# pololuLaserDrv.net
KiCad netlist of a schematic drawn in EAGLE
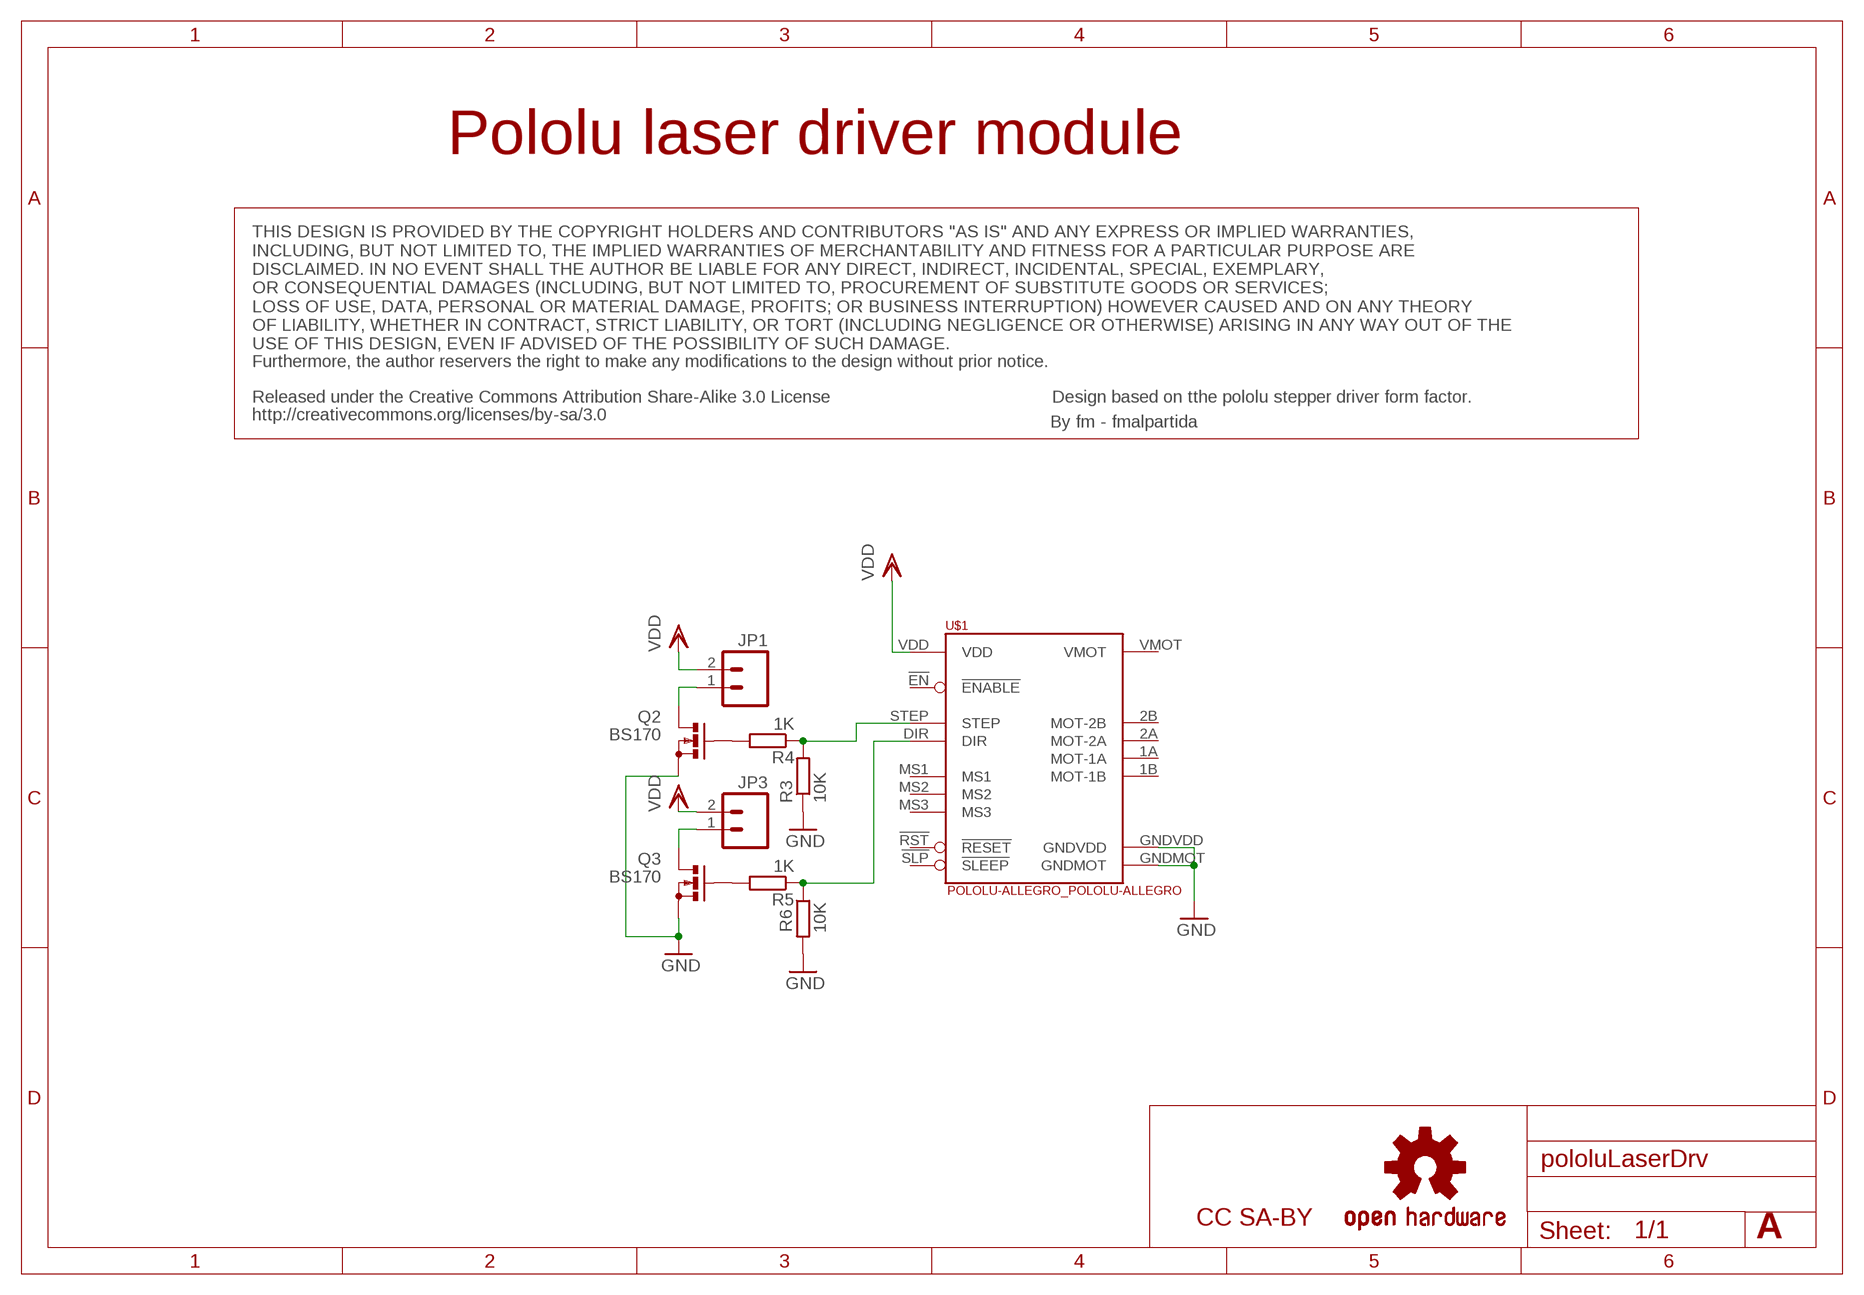
[diagram p0: schematic, sheet 1]

(export (version "E")
  (design (tool "Eeschema 10.0.6"))
  (components
    (comp (ref "JP1")
      (value "M02PTH")
      (footprint "eagle-import:1X02")
      (libsource (lib "eagle-import") (part "M02PTH"))
    )
    (comp (ref "JP3")
      (value "M02PTH")
      (footprint "eagle-import:1X02")
      (libsource (lib "eagle-import") (part "M02PTH"))
    )
    (comp (ref "Q2")
      (value "BS170")
      (footprint "eagle-import:SOT54E")
      (libsource (lib "eagle-import") (part "BS170"))
    )
    (comp (ref "Q3")
      (value "BS170")
      (footprint "eagle-import:SOT54E")
      (libsource (lib "eagle-import") (part "BS170"))
    )
    (comp (ref "R3")
      (value "10K")
      (footprint "eagle-import:0204_5")
      (libsource (lib "eagle-import") (part "R-EU_0204/5"))
    )
    (comp (ref "R4")
      (value "1K")
      (footprint "eagle-import:0204_5")
      (libsource (lib "eagle-import") (part "R-EU_0204/5"))
    )
    (comp (ref "R5")
      (value "1K")
      (footprint "eagle-import:0204_5")
      (libsource (lib "eagle-import") (part "R-EU_0204/5"))
    )
    (comp (ref "R6")
      (value "10K")
      (footprint "eagle-import:0204_5")
      (libsource (lib "eagle-import") (part "R-EU_0204/5"))
    )
    (comp (ref "U$1")
      (value "POLOLU-ALLEGRO_POLOLU-ALLEGRO")
      (footprint "eagle-import:POLOLU-ALLEGRO_POLOLU-ALLEGRO-PTH")
      (libsource (lib "eagle-import") (part "POLOLU-ALLEGRO_POLOLU-ALLEGRO"))
    )
    (comp (ref "U$2")
      (value "OSHW-LOGOS")
      (footprint "eagle-import:OSHW-LOGO-S")
      (libsource (lib "eagle-import") (part "OSHW-LOGOS"))
    )
  )
  (nets
    (net (code "1") (name "/MOT-1A") (class "Default")
      (node (ref "U$1") (pin "1A") (pinfunction "MOT-1A_1A") (pintype "power_in"))
    )
    (net (code "2") (name "/MOT-1B") (class "Default")
      (node (ref "U$1") (pin "1B") (pinfunction "MOT-1B_1B") (pintype "power_in"))
    )
    (net (code "3") (name "/MOT-2A") (class "Default")
      (node (ref "U$1") (pin "2A") (pinfunction "MOT-2A_2A") (pintype "power_in"))
    )
    (net (code "4") (name "/MOT-2B") (class "Default")
      (node (ref "U$1") (pin "2B") (pinfunction "MOT-2B_2B") (pintype "power_in"))
    )
    (net (code "5") (name "/VMOT") (class "Default")
      (node (ref "U$1") (pin "VMOT") (pinfunction "VMOT_VMOT") (pintype "power_in"))
    )
    (net (code "6") (name "GND") (class "Default")
      (node (ref "Q2") (pin "S") (pinfunction "S_S") (pintype "passive"))
      (node (ref "Q3") (pin "S") (pinfunction "S_S") (pintype "passive"))
      (node (ref "R3") (pin "1") (pinfunction "1_1") (pintype "passive"))
      (node (ref "R6") (pin "2") (pinfunction "2_2") (pintype "passive"))
      (node (ref "U$1") (pin "GNDMOT") (pinfunction "GNDMOT_GNDMOT") (pintype "power_in"))
      (node (ref "U$1") (pin "GNDVDD") (pinfunction "GNDVDD_GNDVDD") (pintype "power_in"))
    )
    (net (code "7") (name "Net-(JP1-Pad1)") (class "Default")
      (node (ref "JP1") (pin "1") (pinfunction "1_1") (pintype "passive"))
      (node (ref "Q2") (pin "D") (pinfunction "D_D") (pintype "passive"))
    )
    (net (code "8") (name "Net-(JP3-Pad1)") (class "Default")
      (node (ref "JP3") (pin "1") (pinfunction "1_1") (pintype "passive"))
      (node (ref "Q3") (pin "D") (pinfunction "D_D") (pintype "passive"))
    )
    (net (code "9") (name "Net-(Q2-PadG)") (class "Default")
      (node (ref "Q2") (pin "G") (pinfunction "G_G") (pintype "passive"))
      (node (ref "R4") (pin "2") (pinfunction "2_2") (pintype "passive"))
    )
    (net (code "10") (name "Net-(Q3-PadG)") (class "Default")
      (node (ref "Q3") (pin "G") (pinfunction "G_G") (pintype "passive"))
      (node (ref "R5") (pin "2") (pinfunction "2_2") (pintype "passive"))
    )
    (net (code "11") (name "Net-(R3-Pad2)") (class "Default")
      (node (ref "R3") (pin "2") (pinfunction "2_2") (pintype "passive"))
      (node (ref "R4") (pin "1") (pinfunction "1_1") (pintype "passive"))
      (node (ref "U$1") (pin "STEP") (pinfunction "STEP_STEP") (pintype "bidirectional"))
    )
    (net (code "12") (name "Net-(R5-Pad1)") (class "Default")
      (node (ref "R5") (pin "1") (pinfunction "1_1") (pintype "passive"))
      (node (ref "R6") (pin "1") (pinfunction "1_1") (pintype "passive"))
      (node (ref "U$1") (pin "DIR") (pinfunction "DIR_DIR") (pintype "bidirectional"))
    )
    (net (code "13") (name "VDD") (class "Default")
      (node (ref "JP1") (pin "2") (pinfunction "2_2") (pintype "passive"))
      (node (ref "JP3") (pin "2") (pinfunction "2_2") (pintype "passive"))
      (node (ref "U$1") (pin "VDD") (pinfunction "VDD_VDD") (pintype "power_in"))
    )
    (net (code "14") (name "unconnected-(U$1-PadMS1)") (class "Default")
      (node (ref "U$1") (pin "MS1") (pinfunction "MS1_MS1") (pintype "input"))
    )
    (net (code "15") (name "unconnected-(U$1-PadMS2)") (class "Default")
      (node (ref "U$1") (pin "MS2") (pinfunction "MS2_MS2") (pintype "input"))
    )
    (net (code "16") (name "unconnected-(U$1-PadMS3)") (class "Default")
      (node (ref "U$1") (pin "MS3") (pinfunction "MS3_MS3") (pintype "input"))
    )
    (net (code "17") (name "unconnected-(U$1-~{ENABLE}-Pad!EN)") (class "Default")
      (node (ref "U$1") (pin "!EN") (pinfunction "~{ENABLE}_!EN") (pintype "input"))
    )
    (net (code "18") (name "unconnected-(U$1-~{RESET}-Pad!RST)") (class "Default")
      (node (ref "U$1") (pin "!RST") (pinfunction "~{RESET}_!RST") (pintype "input"))
    )
    (net (code "19") (name "unconnected-(U$1-~{SLEEP}-Pad!SLP)") (class "Default")
      (node (ref "U$1") (pin "!SLP") (pinfunction "~{SLEEP}_!SLP") (pintype "input"))
    )
  )
)
